# SiPM_ASSY.net
KiCad netlist of a schematic drawn in Altium Designer
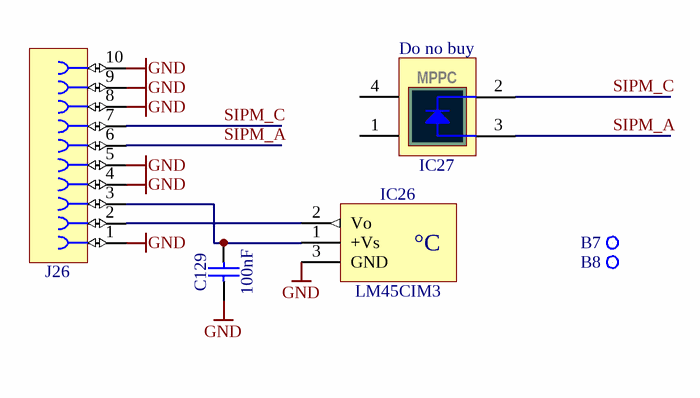
[diagram p0: SiPM_ASSY.SchDoc]

(export (version "E")
  (design (tool "Eeschema 10.0.6"))
  (components
    (comp (ref "B7")
      (value "Plated Hole")
      (footprint "MTG270_500")
      (description "Single Terminal Socket")
      (fields (field (name "PART NUMBER") "PLATED_HOLE2.7_PAD5.0") (field (name "AUTHOR") "CERN DEM JMW"))
      (libsource (lib "Eletro-mechanical") (part "Single Terminal Socket"))
    )
    (comp (ref "B8")
      (value "Plated Hole")
      (footprint "MTG270_500")
      (description "Single Terminal Socket")
      (fields (field (name "PART NUMBER") "PLATED_HOLE2.7_PAD5.0") (field (name "AUTHOR") "CERN DEM JMW"))
      (libsource (lib "Eletro-mechanical") (part "Single Terminal Socket"))
    )
    (comp (ref "C129")
      (value "100nF")
      (footprint "CAPC1005X55N")
      (description "Non-polarised capacitor")
      (fields
        (field (name "PART NUMBER") "CC0402_100NF_16V_10%_X7R")
        (field (name "VOLTAGE") "16V")
        (field (name "AUTHOR") "CERN DEM JLC")
      )
      (libsource (lib "Capacitors") (part "Capacitor - non polarized"))
    )
    (comp (ref "IC26")
      (value "LM45CIM3")
      (footprint "SOT95P251X112-3N")
      (description "-20° to +100°C ±3°C Precision Centigrade Temperature Sensors")
      (fields (field (name "MANUFACTURER") "NATIONAL SEMICONDUCTOR") (field (name "AUTHOR") "CERN DEM JLC"))
      (libsource (lib "ICs And Semiconductors") (part "LM45"))
    )
    (comp (ref "IC27")
      (value "Do no buy")
      (footprint "HAMAMATSU_S13360-1325PE")
      (description "MPPC (Multi-Pixel Photon Counter)")
      (fields
        (field (name "PART NUMBER") "S13360-1325PE")
        (field (name "MANUFACTURER") "HAMAMATSU")
        (field (name "AUTHOR") "GK")
      )
      (libsource (lib "LIBRARY_SCH") (part "SENS_S13360-1325PE"))
    )
    (comp (ref "J26")
      (value "FFC/FPC")
      (footprint "MOLEX_52745-1097")
      (description "Connector 10 Female")
      (fields
        (field (name "PART NUMBER") "MOLEX_52745-1097")
        (field (name "MANUFACTURER") "MOLEX")
        (field (name "AUTHOR") "CERN DEM JLC")
      )
      (libsource (lib "Connectors") (part "Connector 10 Female"))
    )
  )
  (nets
    (net (code "1") (name "/SIPM_A") (class "Default")
      (node (ref "IC27") (pin "3") (pinfunction "A_3") (pintype "passive"))
      (node (ref "J26") (pin "6") (pinfunction "6_6") (pintype "bidirectional"))
    )
    (net (code "2") (name "/SIPM_C") (class "Default")
      (node (ref "IC27") (pin "2") (pinfunction "C_2") (pintype "passive"))
      (node (ref "J26") (pin "7") (pinfunction "7_7") (pintype "bidirectional"))
    )
    (net (code "3") (name "GND") (class "Default")
      (node (ref "C129") (pin "1") (pinfunction "1_1") (pintype "passive"))
      (node (ref "IC26") (pin "3") (pinfunction "GND_3") (pintype "power_in"))
      (node (ref "J26") (pin "1") (pinfunction "1_1") (pintype "bidirectional"))
      (node (ref "J26") (pin "10") (pinfunction "10_10") (pintype "bidirectional"))
      (node (ref "J26") (pin "4") (pinfunction "4_4") (pintype "bidirectional"))
      (node (ref "J26") (pin "5") (pinfunction "5_5") (pintype "bidirectional"))
      (node (ref "J26") (pin "8") (pinfunction "8_8") (pintype "bidirectional"))
      (node (ref "J26") (pin "9") (pinfunction "9_9") (pintype "bidirectional"))
    )
    (net (code "4") (name "Net-(IC26-+Vs)") (class "Default")
      (node (ref "C129") (pin "2") (pinfunction "2_2") (pintype "passive"))
      (node (ref "IC26") (pin "1") (pinfunction "+Vs_1") (pintype "power_in"))
      (node (ref "J26") (pin "3") (pinfunction "3_3") (pintype "bidirectional"))
    )
    (net (code "5") (name "Net-(IC26-Vo)") (class "Default")
      (node (ref "IC26") (pin "2") (pinfunction "Vo_2") (pintype "output"))
      (node (ref "J26") (pin "2") (pinfunction "2_2") (pintype "bidirectional"))
    )
    (net (code "6") (name "unconnected-(B7-Pad1)") (class "Default")
      (node (ref "B7") (pin "1") (pinfunction "1_1") (pintype "bidirectional"))
    )
    (net (code "7") (name "unconnected-(B8-Pad1)") (class "Default")
      (node (ref "B8") (pin "1") (pinfunction "1_1") (pintype "bidirectional"))
    )
    (net (code "8") (name "unconnected-(IC27-NC-Pad1)") (class "Default")
      (node (ref "IC27") (pin "1") (pinfunction "NC_1") (pintype "passive"))
    )
    (net (code "9") (name "unconnected-(IC27-NC-Pad4)") (class "Default")
      (node (ref "IC27") (pin "4") (pinfunction "NC_4") (pintype "passive"))
    )
  )
)
